# PowerSupply_404_JustBuck.net
KiCad netlist of a schematic drawn in Altium Designer
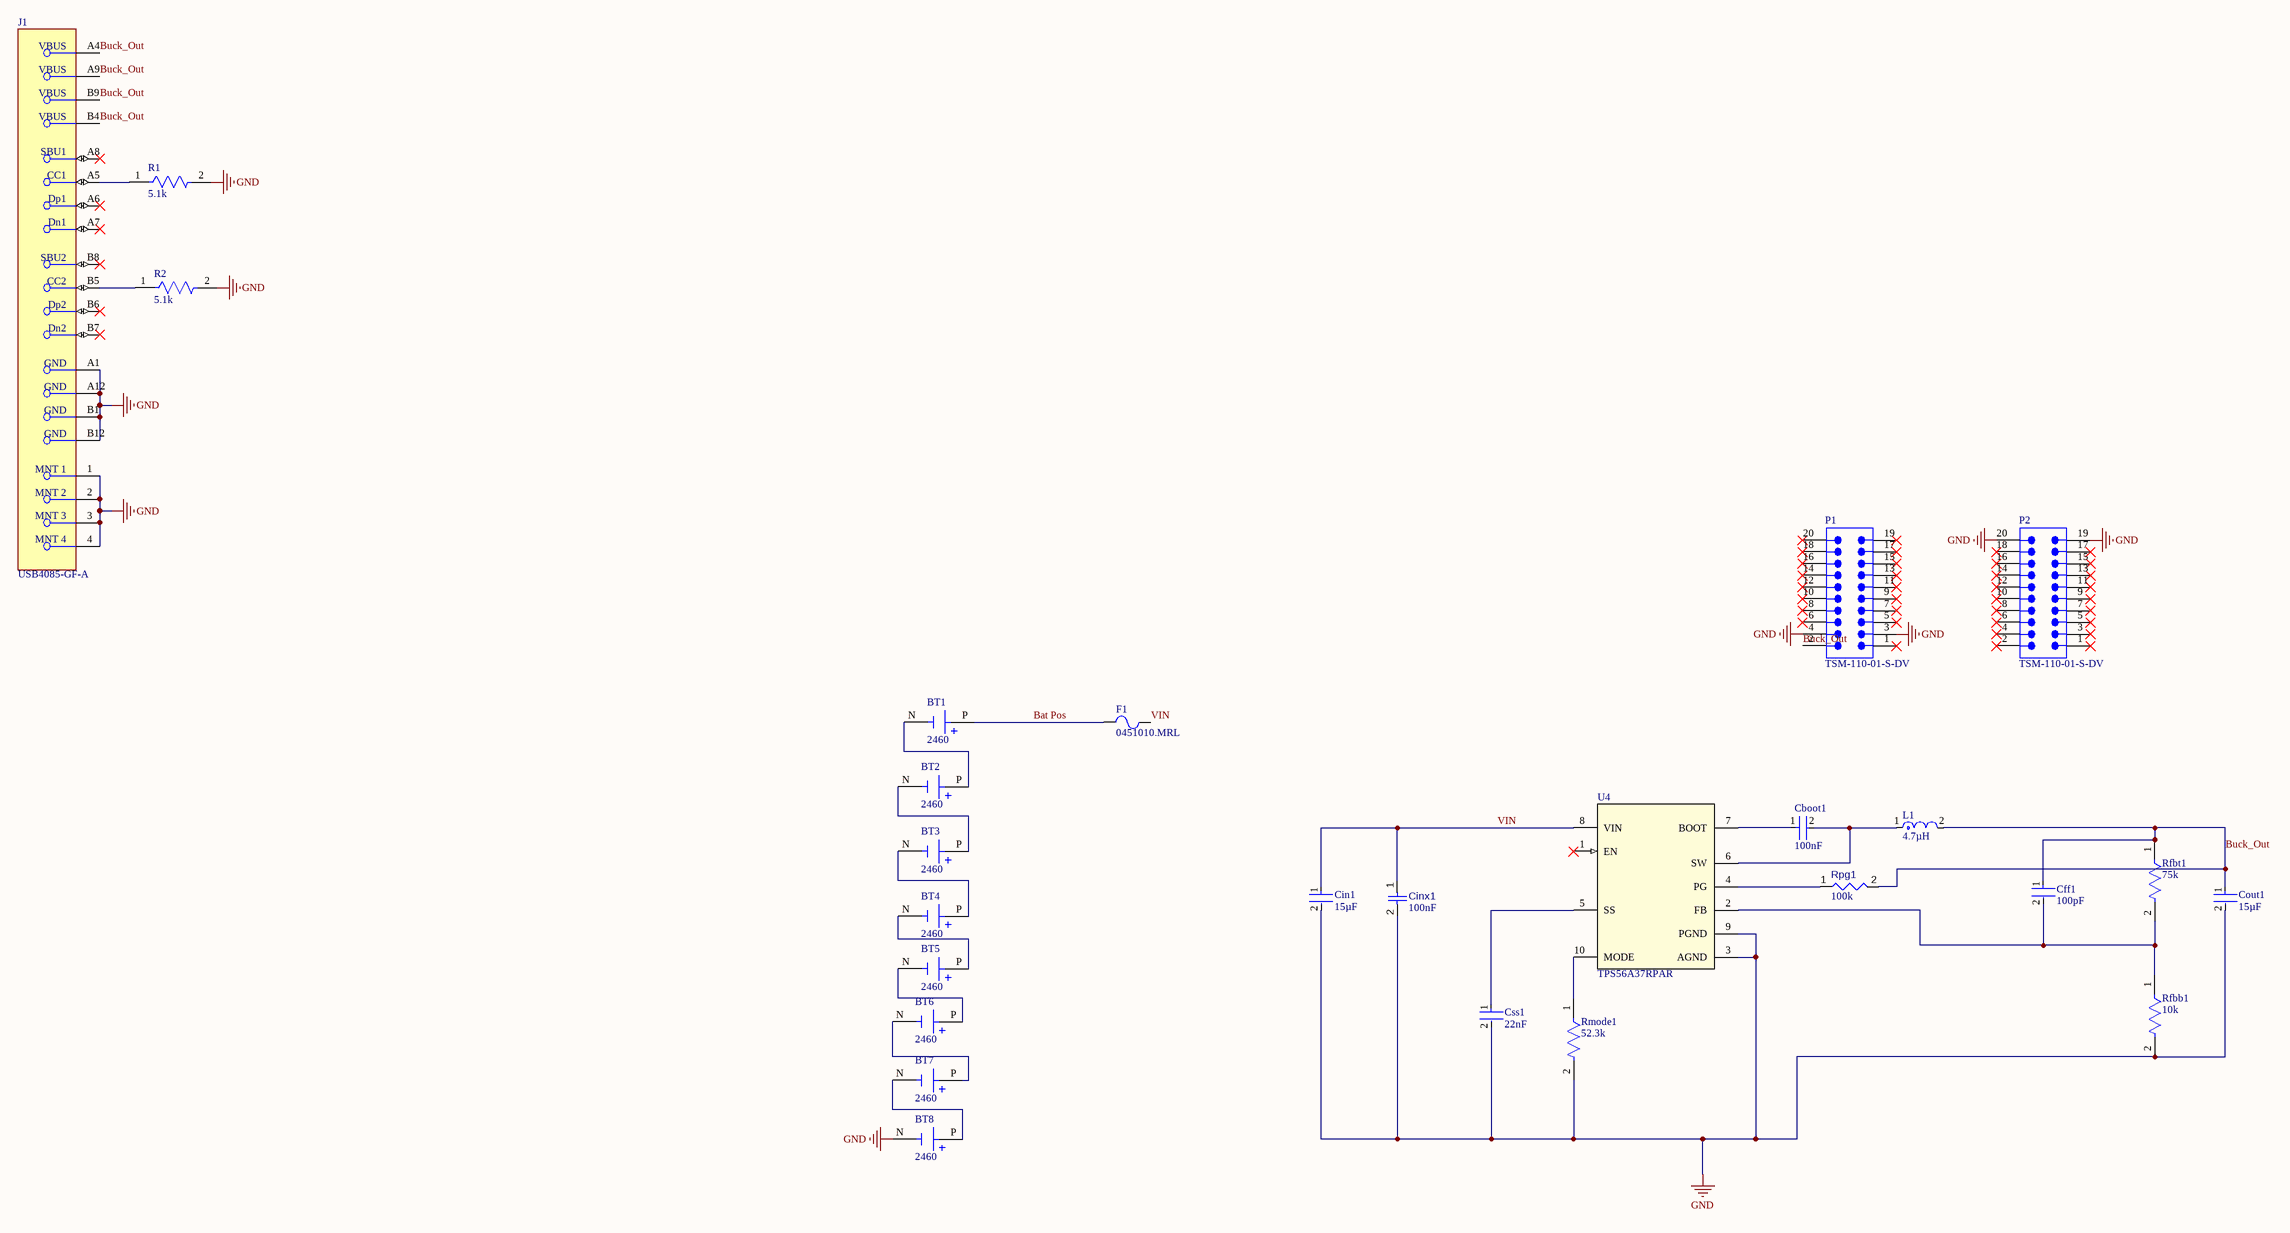
[diagram p0: PowerSupply_404_JustBuck.SchDoc]

(export (version "E")
  (design (tool "Eeschema 10.0.6"))
  (components
    (comp (ref "BT1")
      (value "2460")
      (footprint "BAT_2460")
      (description "Battery Holder, AA, Polypropylene, PC Mount, 1, Spring, PC Lug")
      (fields (field (name "MF") "Keystone Electronics"))
      (libsource (lib "ECEN_403_Workspace_1") (part "2460"))
    )
    (comp (ref "BT2")
      (value "2460")
      (footprint "BAT_2460")
      (description "Battery Holder, AA, Polypropylene, PC Mount, 1, Spring, PC Lug")
      (fields (field (name "MF") "Keystone Electronics"))
      (libsource (lib "ECEN_403_Workspace_1") (part "2460"))
    )
    (comp (ref "BT3")
      (value "2460")
      (footprint "BAT_2460")
      (description "Battery Holder, AA, Polypropylene, PC Mount, 1, Spring, PC Lug")
      (fields (field (name "MF") "Keystone Electronics"))
      (libsource (lib "ECEN_403_Workspace_1") (part "2460"))
    )
    (comp (ref "BT4")
      (value "2460")
      (footprint "BAT_2460")
      (description "Battery Holder, AA, Polypropylene, PC Mount, 1, Spring, PC Lug")
      (fields (field (name "MF") "Keystone Electronics"))
      (libsource (lib "ECEN_403_Workspace_1") (part "2460"))
    )
    (comp (ref "BT5")
      (value "2460")
      (footprint "BAT_2460")
      (description "Battery Holder, AA, Polypropylene, PC Mount, 1, Spring, PC Lug")
      (fields (field (name "MF") "Keystone Electronics"))
      (libsource (lib "ECEN_403_Workspace_1") (part "2460"))
    )
    (comp (ref "BT6")
      (value "2460")
      (footprint "BAT_2460")
      (description "Battery Holder, AA, Polypropylene, PC Mount, 1, Spring, PC Lug")
      (fields (field (name "MF") "Keystone Electronics"))
      (libsource (lib "ECEN_403_Workspace_1") (part "2460"))
    )
    (comp (ref "BT7")
      (value "2460")
      (footprint "BAT_2460")
      (description "Battery Holder, AA, Polypropylene, PC Mount, 1, Spring, PC Lug")
      (fields (field (name "MF") "Keystone Electronics"))
      (libsource (lib "ECEN_403_Workspace_1") (part "2460"))
    )
    (comp (ref "BT8")
      (value "2460")
      (footprint "BAT_2460")
      (description "Battery Holder, AA, Polypropylene, PC Mount, 1, Spring, PC Lug")
      (fields (field (name "MF") "Keystone Electronics"))
      (libsource (lib "ECEN_403_Workspace_1") (part "2460"))
    )
    (comp (ref "Cboot1")
      (value "100nF")
      (footprint "FP-C0805C-DN-IPC_A")
      (description "50V 100nF X7R ±20% 0805 Multilayer Ceramic Capacitors MLCC - SMD/SMT ROHS")
      (fields (field (name "VOLTAGE") "50V") (field (name "TOLERANCE") "20%"))
      (libsource (lib "ECEN_403_Workspace_1") (part "b4654b650e69147ec39a6b967a45e02"))
    )
    (comp (ref "Cff1")
      (value "100pF")
      (footprint "FP-C0805C-DN-IPC_A")
      (description "50V 100pF C0G ±10% 0805 Multilayer Ceramic Capacitors MLCC - SMD/SMT ROHS")
      (fields (field (name "TOLERANCE") "10%") (field (name "VOLTAGE") "50V"))
      (libsource (lib "ECEN_403_Workspace_1") (part "b4654b650e69147ec39a6b967a45e02"))
    )
    (comp (ref "Cin1")
      (value "15µF")
      (footprint "FP-C2012-125-0_2-IPC_A")
      (description "35V 15uF X5R 卤20% 0805 Multilayer Ceramic Capacitors MLCC - SMD/SMT ROHS")
      (fields (field (name "TOLERANCE") "20%") (field (name "Comment") "C2012X5R1V156M125AC"))
      (libsource (lib "ECEN_403_Workspace_1") (part "b4654b650e69147ec39a6b967a45e02"))
    )
    (comp (ref "Cinx1")
      (value "100nF")
      (footprint "CAPC2013X95X50LL10T25")
      (description "Chip Capacitor, 100 nF, +/- 10%, 50 V, 0805 (2012 Metric)")
      (fields (field (name "TOLERANCE") "10%") (field (name "Comment") "CC0805KRX7R9BB104"))
      (libsource (lib "ECEN_403_Workspace_1") (part "CAP-NP-2"))
    )
    (comp (ref "Cout1")
      (value "15µF")
      (footprint "FP-C3225-250-0_4-IPC_A")
      (description "16V 15uF X5R 卤20% 1210 Multilayer Ceramic Capacitors MLCC - SMD/SMT ROHS")
      (fields (field (name "TOLERANCE") "20%") (field (name "Comment") "C3225X5R1C156M250AA"))
      (libsource (lib "ECEN_403_Workspace_1") (part "02cd4be3c70576c341d710602a673aa"))
    )
    (comp (ref "Css1")
      (value "22nF")
      (footprint "FP-C0603C-CF-IPC_B")
      (description "Multilayer Ceramic Capacitors MLCC - SMD/SMT 16V 0.022uF X7R 0603 10%")
      (fields (field (name "TOLERANCE") "10%") (field (name "Comment") "C0603C223K4RACTU"))
      (libsource (lib "ECEN_403_Workspace_1") (part "b4654b650e69147ec39a6b967a45e02"))
    )
    (comp (ref "F1")
      (value "0451010.MRL")
      (footprint "LFUS-45X_V")
      (description "Fuse Chip Very Fast Acting 10A 125V SMD Solder Pad 2410 Ceramic T/R CSA/PSE/UL")
      (libsource (lib "ECEN_403_Workspace_1") (part "FUSE-2"))
    )
    (comp (ref "J1")
      (value "USB4085-GF-A")
      (footprint "FP-USB4085-GF-A-MFG")
      (description "USB Connector, 16 Contact(s), Female, Right Angle, Solder Terminal, Locking, Receptacle")
      (libsource (lib "ECEN_403_Workspace_1") (part "10fa745527c8b974685cbca3c197132"))
    )
    (comp (ref "L1")
      (value "4.7µH")
      (footprint "FP-XAL6060-472MEC-MFG")
      (description "XAL6060-472MEC; General Purpose Inductor, 4.7uH, 20%, 1 Element, Composite-Core, SMD, 2625")
      (fields (field (name "TOLERANCE") "20%") (field (name "Comment") "XAL6060-472MEC"))
      (libsource (lib "ECEN_403_Workspace_1") (part "4cc4b267dca4c8e51f7102f422741d8"))
    )
    (comp (ref "P1")
      (value "TSM-110-01-S-DV")
      (footprint "SMTC-TSM-110-01-X-DV")
      (fields (field (name "MANUFACTURER") "Samtec"))
      (libsource (lib "ECEN_403_Workspace_1") (part "CMP-1024-00283-1"))
    )
    (comp (ref "P2")
      (value "TSM-110-01-S-DV")
      (footprint "SMTC-TSM-110-01-X-DV")
      (fields (field (name "MANUFACTURER") "Samtec"))
      (libsource (lib "ECEN_403_Workspace_1") (part "CMP-1024-00283-1"))
    )
    (comp (ref "R1")
      (value "5.1k")
      (footprint "FP-RT0603-IPC_C")
      (description "Fixed Resistor, Thin Film, 0.1W, 5100ohm, 75V, 1% +/-Tol, 50ppm/Cel, Surface Mount, 0603")
      (fields (field (name "TOLERANCE") "1%") (field (name "Comment") "RT0603FRE075K1L"))
      (libsource (lib "ECEN_403_Workspace_1") (part "1029c3af85768c4190bb7ad29bc67b5"))
    )
    (comp (ref "R2")
      (value "5.1k")
      (footprint "FP-RT0603-IPC_C")
      (description "Fixed Resistor, Thin Film, 0.1W, 5100ohm, 75V, 1% +/-Tol, 50ppm/Cel, Surface Mount, 0603")
      (fields (field (name "TOLERANCE") "1%") (field (name "Comment") "RT0603FRE075K1L"))
      (libsource (lib "ECEN_403_Workspace_1") (part "1029c3af85768c4190bb7ad29bc67b5"))
    )
    (comp (ref "Rfbb1")
      (value "10k")
      (footprint "FP-CRCW0805-e3-IPC_A")
      (description "Res Thick Film 0805 10K Ohm 1% 0.125W(1/8W) ±100ppm/C Pad SMD Automotive T/R")
      (fields (field (name "TOLERANCE") "1%") (field (name "Comment") "CRCW080510K0FKEA"))
      (libsource (lib "ECEN_403_Workspace_1") (part "1029c3af85768c4190bb7ad29bc67b5"))
    )
    (comp (ref "Rfbt1")
      (value "75k")
      (footprint "FP-CRCW0805-e3-IPC_A")
      (description "Res Thick Film 0805 75K Ohm 1% 1/8W ±100ppm/°C Molded SMD Paper T/R")
      (fields (field (name "TOLERANCE") "1%") (field (name "Comment") "CRCW080575K0FKEA"))
      (libsource (lib "ECEN_403_Workspace_1") (part "1029c3af85768c4190bb7ad29bc67b5"))
    )
    (comp (ref "Rmode1")
      (value "52.3k")
      (footprint "FP-CRCW0603-e3-IPC_C")
      (description "100mW Thick Film Resistors 75V ±1% ±100ppm/℃ 52.3kΩ 0603 Chip Resistor - Surface Mount ROHS")
      (fields (field (name "TOLERANCE") "1%") (field (name "Comment") "CRCW060352K3FKEA"))
      (libsource (lib "ECEN_403_Workspace_1") (part "1029c3af85768c4190bb7ad29bc67b5"))
    )
    (comp (ref "Rpg1")
      (value "100k")
      (footprint "RESC2013X70X40ML20T20")
      (description "Chip Resistor, 100 KOhm, +/- 1%, 0.125 W, -55 to 155 degC, 0805 (2012 Metric)")
      (fields (field (name "POWER") "125mW") (field (name "TOLERANCE") "1%"))
      (libsource (lib "ECEN_403_Workspace_1") (part "RES-2"))
    )
    (comp (ref "U4")
      (value "TPS56A37RPAR")
      (footprint "RPA0010A-MFG")
      (description "4.5V to 28V input, 10A synchronous buck converter 10-VQFN-HR -40 to 150")
      (fields (field (name "COPYRIGHT") "Copyright (C) 2025 Ultra Librarian. All rights reserved."))
      (libsource (lib "ECEN_403_Workspace_1") (part "TPS56A37RPAR"))
    )
  )
  (nets
    (net (code "1") (name "/Bat Pos") (class "Default")
      (node (ref "BT1") (pin "P") (pinfunction "POS_P") (pintype "passive"))
      (node (ref "F1") (pin "1") (pinfunction "1_1") (pintype "passive"))
    )
    (net (code "2") (name "/Buck_Out") (class "Default")
      (node (ref "Cff1") (pin "1") (pinfunction "1_1") (pintype "passive"))
      (node (ref "Cout1") (pin "1") (pinfunction "1_1") (pintype "passive"))
      (node (ref "J1") (pin "A4") (pinfunction "VBUS_A4") (pintype "power_in"))
      (node (ref "J1") (pin "A9") (pinfunction "VBUS_A9") (pintype "power_in"))
      (node (ref "J1") (pin "B4") (pinfunction "VBUS_B4") (pintype "power_in"))
      (node (ref "J1") (pin "B9") (pinfunction "VBUS_B9") (pintype "power_in"))
      (node (ref "L1") (pin "2") (pinfunction "2_2") (pintype "passive"))
      (node (ref "P1") (pin "2") (pinfunction "2_2") (pintype "passive"))
      (node (ref "Rfbt1") (pin "1") (pinfunction "1_1") (pintype "passive"))
      (node (ref "Rpg1") (pin "2") (pinfunction "2_2") (pintype "passive"))
    )
    (net (code "3") (name "/VIN") (class "Default")
      (node (ref "Cin1") (pin "1") (pinfunction "1_1") (pintype "passive"))
      (node (ref "Cinx1") (pin "1") (pinfunction "1_1") (pintype "passive"))
      (node (ref "F1") (pin "2") (pinfunction "2_2") (pintype "passive"))
      (node (ref "U4") (pin "8") (pinfunction "VIN_8") (pintype "power_in"))
    )
    (net (code "4") (name "GND") (class "Default")
      (node (ref "BT8") (pin "N") (pinfunction "NEG_N") (pintype "passive"))
      (node (ref "Cin1") (pin "2") (pinfunction "2_2") (pintype "passive"))
      (node (ref "Cinx1") (pin "2") (pinfunction "2_2") (pintype "passive"))
      (node (ref "Cout1") (pin "2") (pinfunction "2_2") (pintype "passive"))
      (node (ref "Css1") (pin "2") (pinfunction "2_2") (pintype "passive"))
      (node (ref "J1") (pin "1") (pinfunction "MNT_1_1") (pintype "passive"))
      (node (ref "J1") (pin "2") (pinfunction "MNT_2_2") (pintype "passive"))
      (node (ref "J1") (pin "3") (pinfunction "MNT_3_3") (pintype "passive"))
      (node (ref "J1") (pin "4") (pinfunction "MNT_4_4") (pintype "passive"))
      (node (ref "J1") (pin "A1") (pinfunction "GND_A1") (pintype "power_in"))
      (node (ref "J1") (pin "A12") (pinfunction "GND_A12") (pintype "power_in"))
      (node (ref "J1") (pin "B1") (pinfunction "GND_B1") (pintype "power_in"))
      (node (ref "J1") (pin "B12") (pinfunction "GND_B12") (pintype "power_in"))
      (node (ref "P1") (pin "3") (pinfunction "3_3") (pintype "passive"))
      (node (ref "P1") (pin "4") (pinfunction "4_4") (pintype "passive"))
      (node (ref "P2") (pin "19") (pinfunction "19_19") (pintype "passive"))
      (node (ref "P2") (pin "20") (pinfunction "20_20") (pintype "passive"))
      (node (ref "R1") (pin "2") (pinfunction "2_2") (pintype "passive"))
      (node (ref "R2") (pin "2") (pinfunction "2_2") (pintype "passive"))
      (node (ref "Rfbb1") (pin "2") (pinfunction "2_2") (pintype "passive"))
      (node (ref "Rmode1") (pin "2") (pinfunction "2_2") (pintype "passive"))
      (node (ref "U4") (pin "3") (pinfunction "AGND_3") (pintype "power_in"))
      (node (ref "U4") (pin "9") (pinfunction "PGND_9") (pintype "power_in"))
    )
    (net (code "5") (name "Net-(BT1-NEG)") (class "Default")
      (node (ref "BT1") (pin "N") (pinfunction "NEG_N") (pintype "passive"))
      (node (ref "BT2") (pin "P") (pinfunction "POS_P") (pintype "passive"))
    )
    (net (code "6") (name "Net-(BT2-NEG)") (class "Default")
      (node (ref "BT2") (pin "N") (pinfunction "NEG_N") (pintype "passive"))
      (node (ref "BT3") (pin "P") (pinfunction "POS_P") (pintype "passive"))
    )
    (net (code "7") (name "Net-(BT3-NEG)") (class "Default")
      (node (ref "BT3") (pin "N") (pinfunction "NEG_N") (pintype "passive"))
      (node (ref "BT4") (pin "P") (pinfunction "POS_P") (pintype "passive"))
    )
    (net (code "8") (name "Net-(BT4-NEG)") (class "Default")
      (node (ref "BT4") (pin "N") (pinfunction "NEG_N") (pintype "passive"))
      (node (ref "BT5") (pin "P") (pinfunction "POS_P") (pintype "passive"))
    )
    (net (code "9") (name "Net-(BT5-NEG)") (class "Default")
      (node (ref "BT5") (pin "N") (pinfunction "NEG_N") (pintype "passive"))
      (node (ref "BT6") (pin "P") (pinfunction "POS_P") (pintype "passive"))
    )
    (net (code "10") (name "Net-(BT6-NEG)") (class "Default")
      (node (ref "BT6") (pin "N") (pinfunction "NEG_N") (pintype "passive"))
      (node (ref "BT7") (pin "P") (pinfunction "POS_P") (pintype "passive"))
    )
    (net (code "11") (name "Net-(BT7-NEG)") (class "Default")
      (node (ref "BT7") (pin "N") (pinfunction "NEG_N") (pintype "passive"))
      (node (ref "BT8") (pin "P") (pinfunction "POS_P") (pintype "passive"))
    )
    (net (code "12") (name "Net-(J1-CC1)") (class "Default")
      (node (ref "J1") (pin "A5") (pinfunction "CC1_A5") (pintype "bidirectional"))
      (node (ref "R1") (pin "1") (pinfunction "1_1") (pintype "passive"))
    )
    (net (code "13") (name "Net-(J1-CC2)") (class "Default")
      (node (ref "J1") (pin "B5") (pinfunction "CC2_B5") (pintype "bidirectional"))
      (node (ref "R2") (pin "1") (pinfunction "1_1") (pintype "passive"))
    )
    (net (code "14") (name "Net-(U4-BOOT)") (class "Default")
      (node (ref "Cboot1") (pin "1") (pinfunction "1_1") (pintype "passive"))
      (node (ref "U4") (pin "7") (pinfunction "BOOT_7") (pintype "passive"))
    )
    (net (code "15") (name "Net-(U4-FB)") (class "Default")
      (node (ref "Cff1") (pin "2") (pinfunction "2_2") (pintype "passive"))
      (node (ref "Rfbb1") (pin "1") (pinfunction "1_1") (pintype "passive"))
      (node (ref "Rfbt1") (pin "2") (pinfunction "2_2") (pintype "passive"))
      (node (ref "U4") (pin "2") (pinfunction "FB_2") (pintype "passive"))
    )
    (net (code "16") (name "Net-(U4-MODE)") (class "Default")
      (node (ref "Rmode1") (pin "1") (pinfunction "1_1") (pintype "passive"))
      (node (ref "U4") (pin "10") (pinfunction "MODE_10") (pintype "passive"))
    )
    (net (code "17") (name "Net-(U4-PG)") (class "Default")
      (node (ref "Rpg1") (pin "1") (pinfunction "1_1") (pintype "passive"))
      (node (ref "U4") (pin "4") (pinfunction "PG_4") (pintype "open_collector"))
    )
    (net (code "18") (name "Net-(U4-SS)") (class "Default")
      (node (ref "Css1") (pin "1") (pinfunction "1_1") (pintype "passive"))
      (node (ref "U4") (pin "5") (pinfunction "SS_5") (pintype "passive"))
    )
    (net (code "19") (name "Net-(U4-SW)") (class "Default")
      (node (ref "Cboot1") (pin "2") (pinfunction "2_2") (pintype "passive"))
      (node (ref "L1") (pin "1") (pinfunction "1_1") (pintype "passive"))
      (node (ref "U4") (pin "6") (pinfunction "SW_6") (pintype "passive"))
    )
    (net (code "20") (name "unconnected-(J1-Dn1-PadA7)") (class "Default")
      (node (ref "J1") (pin "A7") (pinfunction "Dn1_A7") (pintype "bidirectional+no_connect"))
    )
    (net (code "21") (name "unconnected-(J1-Dn2-PadB7)") (class "Default")
      (node (ref "J1") (pin "B7") (pinfunction "Dn2_B7") (pintype "bidirectional+no_connect"))
    )
    (net (code "22") (name "unconnected-(J1-Dp1-PadA6)") (class "Default")
      (node (ref "J1") (pin "A6") (pinfunction "Dp1_A6") (pintype "bidirectional+no_connect"))
    )
    (net (code "23") (name "unconnected-(J1-Dp2-PadB6)") (class "Default")
      (node (ref "J1") (pin "B6") (pinfunction "Dp2_B6") (pintype "bidirectional+no_connect"))
    )
    (net (code "24") (name "unconnected-(J1-SBU1-PadA8)") (class "Default")
      (node (ref "J1") (pin "A8") (pinfunction "SBU1_A8") (pintype "bidirectional+no_connect"))
    )
    (net (code "25") (name "unconnected-(J1-SBU2-PadB8)") (class "Default")
      (node (ref "J1") (pin "B8") (pinfunction "SBU2_B8") (pintype "bidirectional+no_connect"))
    )
    (net (code "26") (name "unconnected-(P1-Pad1)") (class "Default")
      (node (ref "P1") (pin "1") (pinfunction "1_1") (pintype "passive+no_connect"))
    )
    (net (code "27") (name "unconnected-(P1-Pad5)") (class "Default")
      (node (ref "P1") (pin "5") (pinfunction "5_5") (pintype "passive+no_connect"))
    )
    (net (code "28") (name "unconnected-(P1-Pad6)") (class "Default")
      (node (ref "P1") (pin "6") (pinfunction "6_6") (pintype "passive+no_connect"))
    )
    (net (code "29") (name "unconnected-(P1-Pad7)") (class "Default")
      (node (ref "P1") (pin "7") (pinfunction "7_7") (pintype "passive+no_connect"))
    )
    (net (code "30") (name "unconnected-(P1-Pad8)") (class "Default")
      (node (ref "P1") (pin "8") (pinfunction "8_8") (pintype "passive+no_connect"))
    )
    (net (code "31") (name "unconnected-(P1-Pad9)") (class "Default")
      (node (ref "P1") (pin "9") (pinfunction "9_9") (pintype "passive+no_connect"))
    )
    (net (code "32") (name "unconnected-(P1-Pad10)") (class "Default")
      (node (ref "P1") (pin "10") (pinfunction "10_10") (pintype "passive+no_connect"))
    )
    (net (code "33") (name "unconnected-(P1-Pad11)") (class "Default")
      (node (ref "P1") (pin "11") (pinfunction "11_11") (pintype "passive+no_connect"))
    )
    (net (code "34") (name "unconnected-(P1-Pad12)") (class "Default")
      (node (ref "P1") (pin "12") (pinfunction "12_12") (pintype "passive+no_connect"))
    )
    (net (code "35") (name "unconnected-(P1-Pad13)") (class "Default")
      (node (ref "P1") (pin "13") (pinfunction "13_13") (pintype "passive+no_connect"))
    )
    (net (code "36") (name "unconnected-(P1-Pad14)") (class "Default")
      (node (ref "P1") (pin "14") (pinfunction "14_14") (pintype "passive+no_connect"))
    )
    (net (code "37") (name "unconnected-(P1-Pad15)") (class "Default")
      (node (ref "P1") (pin "15") (pinfunction "15_15") (pintype "passive+no_connect"))
    )
    (net (code "38") (name "unconnected-(P1-Pad16)") (class "Default")
      (node (ref "P1") (pin "16") (pinfunction "16_16") (pintype "passive+no_connect"))
    )
    (net (code "39") (name "unconnected-(P1-Pad17)") (class "Default")
      (node (ref "P1") (pin "17") (pinfunction "17_17") (pintype "passive+no_connect"))
    )
    (net (code "40") (name "unconnected-(P1-Pad18)") (class "Default")
      (node (ref "P1") (pin "18") (pinfunction "18_18") (pintype "passive+no_connect"))
    )
    (net (code "41") (name "unconnected-(P1-Pad19)") (class "Default")
      (node (ref "P1") (pin "19") (pinfunction "19_19") (pintype "passive+no_connect"))
    )
    (net (code "42") (name "unconnected-(P1-Pad20)") (class "Default")
      (node (ref "P1") (pin "20") (pinfunction "20_20") (pintype "passive+no_connect"))
    )
    (net (code "43") (name "unconnected-(P2-Pad1)") (class "Default")
      (node (ref "P2") (pin "1") (pinfunction "1_1") (pintype "passive+no_connect"))
    )
    (net (code "44") (name "unconnected-(P2-Pad2)") (class "Default")
      (node (ref "P2") (pin "2") (pinfunction "2_2") (pintype "passive+no_connect"))
    )
    (net (code "45") (name "unconnected-(P2-Pad3)") (class "Default")
      (node (ref "P2") (pin "3") (pinfunction "3_3") (pintype "passive+no_connect"))
    )
    (net (code "46") (name "unconnected-(P2-Pad4)") (class "Default")
      (node (ref "P2") (pin "4") (pinfunction "4_4") (pintype "passive+no_connect"))
    )
    (net (code "47") (name "unconnected-(P2-Pad5)") (class "Default")
      (node (ref "P2") (pin "5") (pinfunction "5_5") (pintype "passive+no_connect"))
    )
    (net (code "48") (name "unconnected-(P2-Pad6)") (class "Default")
      (node (ref "P2") (pin "6") (pinfunction "6_6") (pintype "passive+no_connect"))
    )
    (net (code "49") (name "unconnected-(P2-Pad7)") (class "Default")
      (node (ref "P2") (pin "7") (pinfunction "7_7") (pintype "passive+no_connect"))
    )
    (net (code "50") (name "unconnected-(P2-Pad8)") (class "Default")
      (node (ref "P2") (pin "8") (pinfunction "8_8") (pintype "passive+no_connect"))
    )
    (net (code "51") (name "unconnected-(P2-Pad9)") (class "Default")
      (node (ref "P2") (pin "9") (pinfunction "9_9") (pintype "passive+no_connect"))
    )
    (net (code "52") (name "unconnected-(P2-Pad10)") (class "Default")
      (node (ref "P2") (pin "10") (pinfunction "10_10") (pintype "passive+no_connect"))
    )
    (net (code "53") (name "unconnected-(P2-Pad11)") (class "Default")
      (node (ref "P2") (pin "11") (pinfunction "11_11") (pintype "passive+no_connect"))
    )
    (net (code "54") (name "unconnected-(P2-Pad12)") (class "Default")
      (node (ref "P2") (pin "12") (pinfunction "12_12") (pintype "passive+no_connect"))
    )
    (net (code "55") (name "unconnected-(P2-Pad13)") (class "Default")
      (node (ref "P2") (pin "13") (pinfunction "13_13") (pintype "passive+no_connect"))
    )
    (net (code "56") (name "unconnected-(P2-Pad14)") (class "Default")
      (node (ref "P2") (pin "14") (pinfunction "14_14") (pintype "passive+no_connect"))
    )
    (net (code "57") (name "unconnected-(P2-Pad15)") (class "Default")
      (node (ref "P2") (pin "15") (pinfunction "15_15") (pintype "passive+no_connect"))
    )
    (net (code "58") (name "unconnected-(P2-Pad16)") (class "Default")
      (node (ref "P2") (pin "16") (pinfunction "16_16") (pintype "passive+no_connect"))
    )
    (net (code "59") (name "unconnected-(P2-Pad17)") (class "Default")
      (node (ref "P2") (pin "17") (pinfunction "17_17") (pintype "passive+no_connect"))
    )
    (net (code "60") (name "unconnected-(P2-Pad18)") (class "Default")
      (node (ref "P2") (pin "18") (pinfunction "18_18") (pintype "passive+no_connect"))
    )
    (net (code "61") (name "unconnected-(U4-EN-Pad1)") (class "Default")
      (node (ref "U4") (pin "1") (pinfunction "EN_1") (pintype "input+no_connect"))
    )
  )
)
